# Project_Vega_Sensors_Schematic.net
KiCad netlist of a schematic drawn in Altium Designer
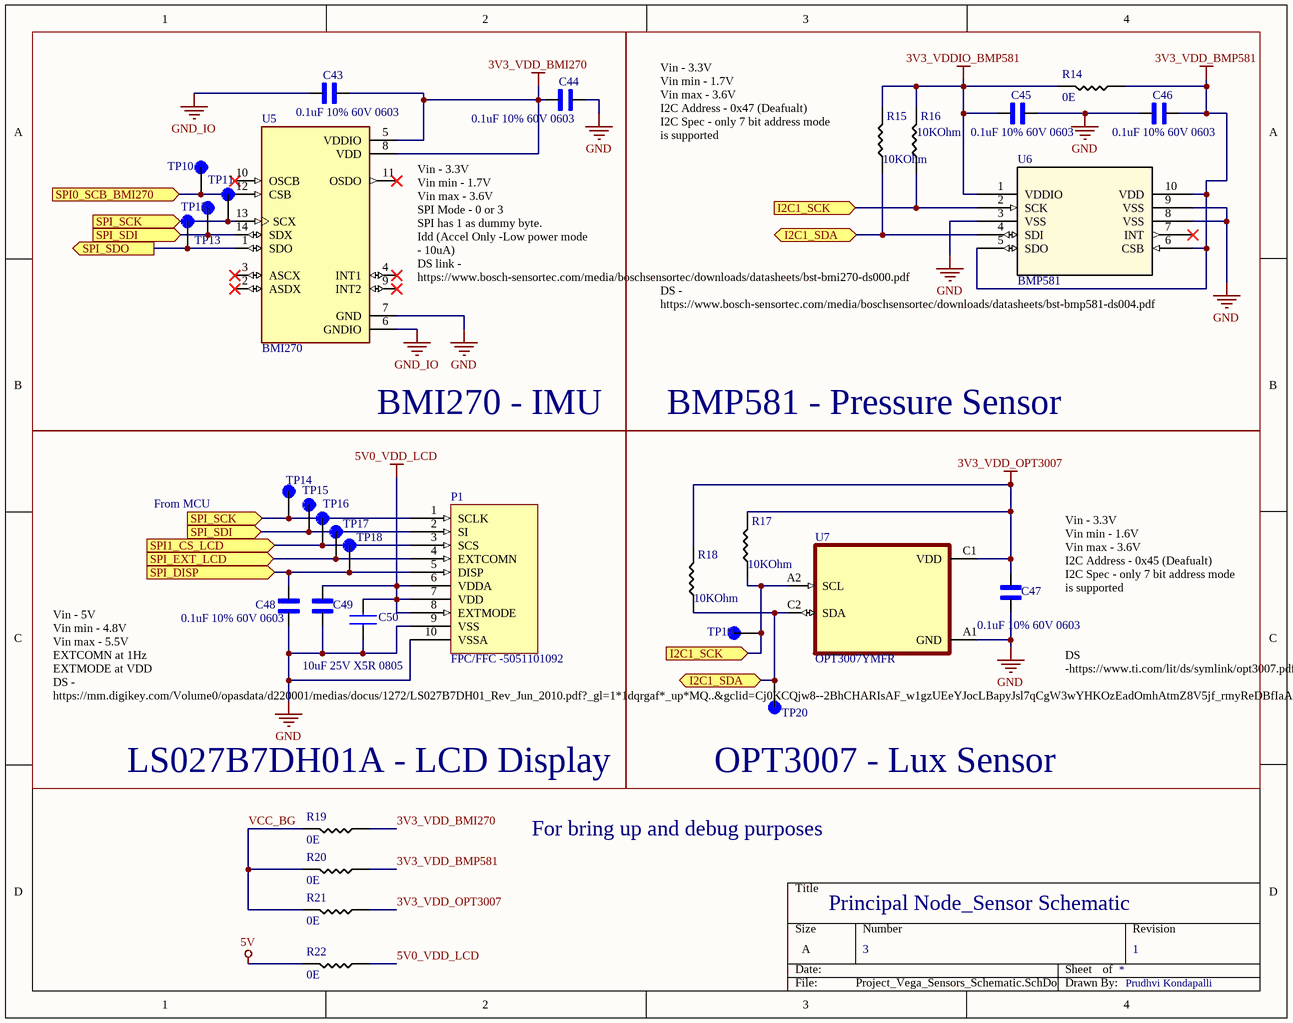
[diagram p0: Project_Vega_Sensors_Schematic.SchDoc]

(export (version "E")
  (design (tool "Eeschema 10.0.6"))
  (components
    (comp (ref "C43")
      (value "0.1uF 10% 60V 0603")
      (footprint "CAPC1608X90")
      (description "0.1 ÂµF Â±10% 50V Ceramic Capacitor X7R 0603 (1608 Metric)")
      (fields (field (name "MF") "Yageo") (field (name "MP") "CC0603KRX7R9BB104"))
      (libsource (lib "Project_Vega") (part "CC0603KRX7R9BB104"))
    )
    (comp (ref "C44")
      (value "0.1uF 10% 60V 0603")
      (footprint "CAPC1608X90")
      (description "0.1 ÂµF Â±10% 50V Ceramic Capacitor X7R 0603 (1608 Metric)")
      (fields (field (name "MF") "Yageo") (field (name "MP") "CC0603KRX7R9BB104"))
      (libsource (lib "Project_Vega") (part "CC0603KRX7R9BB104"))
    )
    (comp (ref "C45")
      (value "0.1uF 10% 60V 0603")
      (footprint "CAPC1608X90")
      (description "0.1 ÂµF Â±10% 50V Ceramic Capacitor X7R 0603 (1608 Metric)")
      (fields (field (name "MF") "Yageo") (field (name "MP") "CC0603KRX7R9BB104"))
      (libsource (lib "Project_Vega") (part "CC0603KRX7R9BB104"))
    )
    (comp (ref "C46")
      (value "0.1uF 10% 60V 0603")
      (footprint "CAPC1608X90")
      (description "0.1 ÂµF Â±10% 50V Ceramic Capacitor X7R 0603 (1608 Metric)")
      (fields (field (name "MF") "Yageo") (field (name "MP") "CC0603KRX7R9BB104"))
      (libsource (lib "Project_Vega") (part "CC0603KRX7R9BB104"))
    )
    (comp (ref "C47")
      (value "0.1uF 10% 60V 0603")
      (footprint "CAPC1608X90")
      (description "0.1 ÂµF Â±10% 50V Ceramic Capacitor X7R 0603 (1608 Metric)")
      (fields (field (name "MF") "Yageo") (field (name "MP") "CC0603KRX7R9BB104"))
      (libsource (lib "") (part "CC0603KRX7R9BB104_1"))
    )
    (comp (ref "C48")
      (value "0.1uF 10% 60V 0603")
      (footprint "CAPC1608X90")
      (description "0.1 ÂµF Â±10% 50V Ceramic Capacitor X7R 0603 (1608 Metric)")
      (fields (field (name "MF") "Yageo") (field (name "MP") "CC0603KRX7R9BB104"))
      (libsource (lib "") (part "CC0603KRX7R9BB104_1"))
    )
    (comp (ref "C49")
      (value "0.1uF 10% 60V 0603")
      (footprint "CAPC1608X90")
      (description "0.1 ÂµF Â±10% 50V Ceramic Capacitor X7R 0603 (1608 Metric)")
      (fields (field (name "MF") "Yageo") (field (name "MP") "CC0603KRX7R9BB104"))
      (libsource (lib "") (part "CC0603KRX7R9BB104_1"))
    )
    (comp (ref "C50")
      (value "10uF 25V X5R 0805")
      (footprint "CAP_0805_2mmX1.25mm")
      (description "Multilayer Ceramic Capacitor, 10 uF, 25 V, +/- 10%, X5R, 0805 [2012 Metric]")
      (fields
        (field (name "MANUFACTURER") "Murata")
        (field (name "MANUFACTURER PART NUMBER") "GRM21BR61E106KA73K")
      )
      (libsource (lib "Project_Vega") (part "GRM21BR61E106KA73K"))
    )
    (comp (ref "P1")
      (value "FPC/FFC -5051101092")
      (footprint "CON_5051101092_MOL")
      (description "10 Position FFC, FPC Connector Contacts, Bottom 0.020\" (0.50mm) Surface Mount, Right Angle")
      (libsource (lib "Project_Vega") (part "5051101092"))
    )
    (comp (ref "R14")
      (value "0E")
      (footprint "1206_Passive_Resitor")
      (description "10 kOhms ±5% 0.25W, 1/4W Chip Resistor 1206 (3216 Metric) Automotive AEC-Q200 Thick Film")
      (fields (field (name "MFR PART #") "RMCF1206FT10K0") (field (name "LCSC PART#") "C17902"))
      (libsource (lib "ECEN5730Lib_2023_05_DS") (part "R_10KOhm_1206"))
    )
    (comp (ref "R15")
      (value "10KOhm")
      (footprint "1206_Passive_Resitor")
      (description "10 kOhms ±5% 0.25W, 1/4W Chip Resistor 1206 (3216 Metric) Automotive AEC-Q200 Thick Film")
      (fields (field (name "MFR PART #") "RMCF1206FT10K0") (field (name "LCSC PART#") "C17902"))
      (libsource (lib "ECEN5730Lib_2023_05_DS") (part "R_10KOhm_1206"))
    )
    (comp (ref "R16")
      (value "10KOhm")
      (footprint "1206_Passive_Resitor")
      (description "10 kOhms ±5% 0.25W, 1/4W Chip Resistor 1206 (3216 Metric) Automotive AEC-Q200 Thick Film")
      (fields (field (name "MFR PART #") "RMCF1206FT10K0") (field (name "LCSC PART#") "C17902"))
      (libsource (lib "ECEN5730Lib_2023_05_DS") (part "R_10KOhm_1206"))
    )
    (comp (ref "R17")
      (value "10KOhm")
      (footprint "1206_Passive_Resitor")
      (description "10 kOhms ±5% 0.25W, 1/4W Chip Resistor 1206 (3216 Metric) Automotive AEC-Q200 Thick Film")
      (fields (field (name "MFR PART #") "RMCF1206FT10K0") (field (name "LCSC PART#") "C17902"))
      (libsource (lib "ECEN5730Lib_2023_05_DS") (part "R_10KOhm_1206"))
    )
    (comp (ref "R18")
      (value "10KOhm")
      (footprint "1206_Passive_Resitor")
      (description "10 kOhms ±5% 0.25W, 1/4W Chip Resistor 1206 (3216 Metric) Automotive AEC-Q200 Thick Film")
      (fields (field (name "MFR PART #") "RMCF1206FT10K0") (field (name "LCSC PART#") "C17902"))
      (libsource (lib "ECEN5730Lib_2023_05_DS") (part "R_10KOhm_1206"))
    )
    (comp (ref "R19")
      (value "0E")
      (footprint "1206_Passive_Resitor")
      (description "10 kOhms ±5% 0.25W, 1/4W Chip Resistor 1206 (3216 Metric) Automotive AEC-Q200 Thick Film")
      (fields (field (name "MFR PART #") "RMCF1206FT10K0") (field (name "LCSC PART#") "C17902"))
      (libsource (lib "ECEN5730Lib_2023_05_DS") (part "R_10KOhm_1206"))
    )
    (comp (ref "R20")
      (value "0E")
      (footprint "1206_Passive_Resitor")
      (description "10 kOhms ±5% 0.25W, 1/4W Chip Resistor 1206 (3216 Metric) Automotive AEC-Q200 Thick Film")
      (fields (field (name "MFR PART #") "RMCF1206FT10K0") (field (name "LCSC PART#") "C17902"))
      (libsource (lib "ECEN5730Lib_2023_05_DS") (part "R_10KOhm_1206"))
    )
    (comp (ref "R21")
      (value "0E")
      (footprint "1206_Passive_Resitor")
      (description "10 kOhms ±5% 0.25W, 1/4W Chip Resistor 1206 (3216 Metric) Automotive AEC-Q200 Thick Film")
      (fields (field (name "MFR PART #") "RMCF1206FT10K0") (field (name "LCSC PART#") "C17902"))
      (libsource (lib "ECEN5730Lib_2023_05_DS") (part "R_10KOhm_1206"))
    )
    (comp (ref "R22")
      (value "0E")
      (footprint "1206_Passive_Resitor")
      (description "10 kOhms ±5% 0.25W, 1/4W Chip Resistor 1206 (3216 Metric) Automotive AEC-Q200 Thick Film")
      (fields (field (name "MFR PART #") "RMCF1206FT10K0") (field (name "LCSC PART#") "C17902"))
      (libsource (lib "ECEN5730Lib_2023_05_DS") (part "R_10KOhm_1206"))
    )
    (comp (ref "TP10")
      (value "Test_point")
      (footprint "TP")
      (description "SMT Test Point- Mininature-1000 pc Reels")
      (fields (field (name "MP") "5019") (field (name "MF") "Keystone Electronics"))
      (libsource (lib "Project_Vega") (part "Test_point"))
    )
    (comp (ref "TP11")
      (value "Test_point")
      (footprint "TP")
      (description "SMT Test Point- Mininature-1000 pc Reels")
      (fields (field (name "MP") "5019") (field (name "MF") "Keystone Electronics"))
      (libsource (lib "Project_Vega") (part "Test_point"))
    )
    (comp (ref "TP12")
      (value "Test_point")
      (footprint "TP")
      (description "SMT Test Point- Mininature-1000 pc Reels")
      (fields (field (name "MP") "5019") (field (name "MF") "Keystone Electronics"))
      (libsource (lib "Project_Vega") (part "Test_point"))
    )
    (comp (ref "TP13")
      (value "Test_point")
      (footprint "TP")
      (description "SMT Test Point- Mininature-1000 pc Reels")
      (fields (field (name "MP") "5019") (field (name "MF") "Keystone Electronics"))
      (libsource (lib "Project_Vega") (part "Test_point"))
    )
    (comp (ref "TP14")
      (value "Test_point")
      (footprint "TP")
      (description "SMT Test Point- Mininature-1000 pc Reels")
      (fields (field (name "MP") "5019") (field (name "MF") "Keystone Electronics"))
      (libsource (lib "Project_Vega") (part "Test_point"))
    )
    (comp (ref "TP15")
      (value "Test_point")
      (footprint "TP")
      (description "SMT Test Point- Mininature-1000 pc Reels")
      (fields (field (name "MP") "5019") (field (name "MF") "Keystone Electronics"))
      (libsource (lib "Project_Vega") (part "Test_point"))
    )
    (comp (ref "TP16")
      (value "Test_point")
      (footprint "TP")
      (description "SMT Test Point- Mininature-1000 pc Reels")
      (fields (field (name "MP") "5019") (field (name "MF") "Keystone Electronics"))
      (libsource (lib "Project_Vega") (part "Test_point"))
    )
    (comp (ref "TP17")
      (value "Test_point")
      (footprint "TP")
      (description "SMT Test Point- Mininature-1000 pc Reels")
      (fields (field (name "MP") "5019") (field (name "MF") "Keystone Electronics"))
      (libsource (lib "Project_Vega") (part "Test_point"))
    )
    (comp (ref "TP18")
      (value "Test_point")
      (footprint "TP")
      (description "SMT Test Point- Mininature-1000 pc Reels")
      (fields (field (name "MP") "5019") (field (name "MF") "Keystone Electronics"))
      (libsource (lib "Project_Vega") (part "Test_point"))
    )
    (comp (ref "TP19")
      (value "Test_point")
      (footprint "TP")
      (description "SMT Test Point- Mininature-1000 pc Reels")
      (fields (field (name "MP") "5019") (field (name "MF") "Keystone Electronics"))
      (libsource (lib "Project_Vega") (part "Test_point"))
    )
    (comp (ref "TP20")
      (value "Test_point")
      (footprint "TP")
      (description "SMT Test Point- Mininature-1000 pc Reels")
      (fields (field (name "MP") "5019") (field (name "MF") "Keystone Electronics"))
      (libsource (lib "Project_Vega") (part "Test_point"))
    )
    (comp (ref "U5")
      (value "BMI270")
      (footprint "XDCR_BMI270")
      (description "Accelerometer, Gyroscope, 6 Axis Sensor IÂ²C, SPI Output")
      (fields (field (name "DIGI-KEY_PART_NUMBER") "828-1091-2-ND") (field (name "MF") "Bosch Sensortec"))
      (libsource (lib "Project_Vega") (part "BMI270"))
    )
    (comp (ref "U6")
      (value "BMP581")
      (footprint "QFN10_BMP581_BOS-M")
      (description "No Description Available")
      (libsource (lib "Project_Vega") (part "BMP581"))
    )
    (comp (ref "U7")
      (value "OPT3007YMFR")
      (footprint "BGA6N60X35P2X3_85X94X22N")
      (description "Ultra-thin ambient light sensor (ALS) with fixed I2C address 6-PICOSTAR -40 to 85")
      (fields (field (name "MF") "Texas Instruments"))
      (libsource (lib "Project_Vega") (part "OPT3007YMFR"))
    )
  )
  (nets
    (net (code "1") (name "/I2C1_SCK") (class "Default")
      (node (ref "R16") (pin "1") (pinfunction "1_1") (pintype "passive"))
      (node (ref "R17") (pin "1") (pinfunction "1_1") (pintype "passive"))
      (node (ref "TP19") (pin "TP") (pinfunction "TP_TP") (pintype "passive"))
      (node (ref "U6") (pin "2") (pinfunction "SCK_2") (pintype "input"))
      (node (ref "U7") (pin "A2") (pinfunction "SCL_A2") (pintype "input"))
    )
    (net (code "2") (name "/I2C1_SDA") (class "Default")
      (node (ref "R15") (pin "1") (pinfunction "1_1") (pintype "passive"))
      (node (ref "R18") (pin "1") (pinfunction "1_1") (pintype "passive"))
      (node (ref "TP20") (pin "TP") (pinfunction "TP_TP") (pintype "passive"))
      (node (ref "U6") (pin "4") (pinfunction "SDI_4") (pintype "bidirectional"))
      (node (ref "U7") (pin "C2") (pinfunction "SDA_C2") (pintype "bidirectional"))
    )
    (net (code "3") (name "/SPI0_SCB_BMI270") (class "Default")
      (node (ref "TP10") (pin "TP") (pinfunction "TP_TP") (pintype "passive"))
      (node (ref "U5") (pin "12") (pinfunction "CSB_12") (pintype "input"))
    )
    (net (code "4") (name "/SPI1_CS_LCD") (class "Default")
      (node (ref "P1") (pin "3") (pinfunction "SCS_3") (pintype "input"))
      (node (ref "TP16") (pin "TP") (pinfunction "TP_TP") (pintype "passive"))
    )
    (net (code "5") (name "/SPI_DISP") (class "Default")
      (node (ref "C48") (pin "2") (pinfunction "2_2") (pintype "passive"))
      (node (ref "P1") (pin "5") (pinfunction "DISP_5") (pintype "input"))
      (node (ref "TP18") (pin "TP") (pinfunction "TP_TP") (pintype "passive"))
    )
    (net (code "6") (name "/SPI_EXT_LCD") (class "Default")
      (node (ref "P1") (pin "4") (pinfunction "EXTCOMN_4") (pintype "input"))
      (node (ref "TP17") (pin "TP") (pinfunction "TP_TP") (pintype "passive"))
    )
    (net (code "7") (name "/SPI_SCK") (class "Default")
      (node (ref "P1") (pin "1") (pinfunction "SCLK_1") (pintype "input"))
      (node (ref "TP11") (pin "TP") (pinfunction "TP_TP") (pintype "passive"))
      (node (ref "TP14") (pin "TP") (pinfunction "TP_TP") (pintype "passive"))
      (node (ref "U5") (pin "13") (pinfunction "SCX_13") (pintype "input"))
    )
    (net (code "8") (name "/SPI_SDI") (class "Default")
      (node (ref "P1") (pin "2") (pinfunction "SI_2") (pintype "input"))
      (node (ref "TP12") (pin "TP") (pinfunction "TP_TP") (pintype "passive"))
      (node (ref "TP15") (pin "TP") (pinfunction "TP_TP") (pintype "passive"))
      (node (ref "U5") (pin "14") (pinfunction "SDX_14") (pintype "bidirectional"))
    )
    (net (code "9") (name "/SPI_SDO") (class "Default")
      (node (ref "TP13") (pin "TP") (pinfunction "TP_TP") (pintype "passive"))
      (node (ref "U5") (pin "1") (pinfunction "SDO_1") (pintype "bidirectional"))
    )
    (net (code "10") (name "/VCC_BG") (class "Default")
      (node (ref "R19") (pin "2") (pinfunction "2_2") (pintype "passive"))
      (node (ref "R20") (pin "2") (pinfunction "2_2") (pintype "passive"))
      (node (ref "R21") (pin "2") (pinfunction "2_2") (pintype "passive"))
    )
    (net (code "11") (name "3V3_VDDIO_BMP581") (class "Default")
      (node (ref "C45") (pin "1") (pinfunction "1_1") (pintype "passive"))
      (node (ref "R14") (pin "2") (pinfunction "2_2") (pintype "passive"))
      (node (ref "R15") (pin "2") (pinfunction "2_2") (pintype "passive"))
      (node (ref "R16") (pin "2") (pinfunction "2_2") (pintype "passive"))
      (node (ref "U6") (pin "1") (pinfunction "VDDIO_1") (pintype "power_in"))
    )
    (net (code "12") (name "3V3_VDD_BMI270") (class "Default")
      (node (ref "C43") (pin "2") (pinfunction "2_2") (pintype "passive"))
      (node (ref "C44") (pin "1") (pinfunction "1_1") (pintype "passive"))
      (node (ref "R19") (pin "1") (pinfunction "1_1") (pintype "passive"))
      (node (ref "U5") (pin "5") (pinfunction "VDDIO_5") (pintype "power_in"))
      (node (ref "U5") (pin "8") (pinfunction "VDD_8") (pintype "power_in"))
    )
    (net (code "13") (name "3V3_VDD_BMP581") (class "Default")
      (node (ref "C46") (pin "2") (pinfunction "2_2") (pintype "passive"))
      (node (ref "R14") (pin "1") (pinfunction "1_1") (pintype "passive"))
      (node (ref "R20") (pin "1") (pinfunction "1_1") (pintype "passive"))
      (node (ref "U6") (pin "10") (pinfunction "VDD_10") (pintype "power_in"))
      (node (ref "U6") (pin "5") (pinfunction "SDO_5") (pintype "bidirectional"))
      (node (ref "U6") (pin "6") (pinfunction "CSB_6") (pintype "input"))
    )
    (net (code "14") (name "3V3_VDD_OPT3007") (class "Default")
      (node (ref "C47") (pin "2") (pinfunction "2_2") (pintype "passive"))
      (node (ref "R17") (pin "2") (pinfunction "2_2") (pintype "passive"))
      (node (ref "R18") (pin "2") (pinfunction "2_2") (pintype "passive"))
      (node (ref "R21") (pin "1") (pinfunction "1_1") (pintype "passive"))
      (node (ref "U7") (pin "C1") (pinfunction "VDD_C1") (pintype "power_in"))
    )
    (net (code "15") (name "5V") (class "Default")
      (node (ref "R22") (pin "2") (pinfunction "2_2") (pintype "passive"))
    )
    (net (code "16") (name "5V0_VDD_LCD") (class "Default")
      (node (ref "C49") (pin "2") (pinfunction "2_2") (pintype "passive"))
      (node (ref "C50") (pin "1") (pinfunction "1_1") (pintype "passive"))
      (node (ref "P1") (pin "6") (pinfunction "VDDA_6") (pintype "power_in"))
      (node (ref "P1") (pin "7") (pinfunction "VDD_7") (pintype "power_in"))
      (node (ref "P1") (pin "8") (pinfunction "EXTMODE_8") (pintype "input"))
      (node (ref "R22") (pin "1") (pinfunction "1_1") (pintype "passive"))
    )
    (net (code "17") (name "GND") (class "Default")
      (node (ref "C44") (pin "2") (pinfunction "2_2") (pintype "passive"))
      (node (ref "C45") (pin "2") (pinfunction "2_2") (pintype "passive"))
      (node (ref "C46") (pin "1") (pinfunction "1_1") (pintype "passive"))
      (node (ref "C47") (pin "1") (pinfunction "1_1") (pintype "passive"))
      (node (ref "C48") (pin "1") (pinfunction "1_1") (pintype "passive"))
      (node (ref "C49") (pin "1") (pinfunction "1_1") (pintype "passive"))
      (node (ref "C50") (pin "2") (pinfunction "2_2") (pintype "passive"))
      (node (ref "P1") (pin "10") (pinfunction "VSSA_10") (pintype "power_in"))
      (node (ref "P1") (pin "9") (pinfunction "VSS_9") (pintype "power_in"))
      (node (ref "U5") (pin "7") (pinfunction "GND_7") (pintype "power_in"))
      (node (ref "U6") (pin "3") (pinfunction "VSS_3") (pintype "power_in"))
      (node (ref "U6") (pin "8") (pinfunction "VSS_8") (pintype "power_in"))
      (node (ref "U6") (pin "9") (pinfunction "VSS_9") (pintype "power_in"))
      (node (ref "U7") (pin "A1") (pinfunction "GND_A1") (pintype "power_in"))
    )
    (net (code "18") (name "GND_IO") (class "Default")
      (node (ref "C43") (pin "1") (pinfunction "1_1") (pintype "passive"))
      (node (ref "U5") (pin "6") (pinfunction "GNDIO_6") (pintype "power_in"))
    )
    (net (code "19") (name "unconnected-(U5-ASCX-Pad3)") (class "Default")
      (node (ref "U5") (pin "3") (pinfunction "ASCX_3") (pintype "bidirectional+no_connect"))
    )
    (net (code "20") (name "unconnected-(U5-ASDX-Pad2)") (class "Default")
      (node (ref "U5") (pin "2") (pinfunction "ASDX_2") (pintype "bidirectional+no_connect"))
    )
    (net (code "21") (name "unconnected-(U5-INT1-Pad4)") (class "Default")
      (node (ref "U5") (pin "4") (pinfunction "INT1_4") (pintype "bidirectional+no_connect"))
    )
    (net (code "22") (name "unconnected-(U5-INT2-Pad9)") (class "Default")
      (node (ref "U5") (pin "9") (pinfunction "INT2_9") (pintype "bidirectional+no_connect"))
    )
    (net (code "23") (name "unconnected-(U5-OSCB-Pad10)") (class "Default")
      (node (ref "U5") (pin "10") (pinfunction "OSCB_10") (pintype "input+no_connect"))
    )
    (net (code "24") (name "unconnected-(U5-OSDO-Pad11)") (class "Default")
      (node (ref "U5") (pin "11") (pinfunction "OSDO_11") (pintype "output+no_connect"))
    )
    (net (code "25") (name "unconnected-(U6-INT-Pad7)") (class "Default")
      (node (ref "U6") (pin "7") (pinfunction "INT_7") (pintype "output+no_connect"))
    )
  )
)
